# UPCNSL-ABS-PVC-DEP-1B.net
KiCad netlist of a schematic drawn in Altium Designer
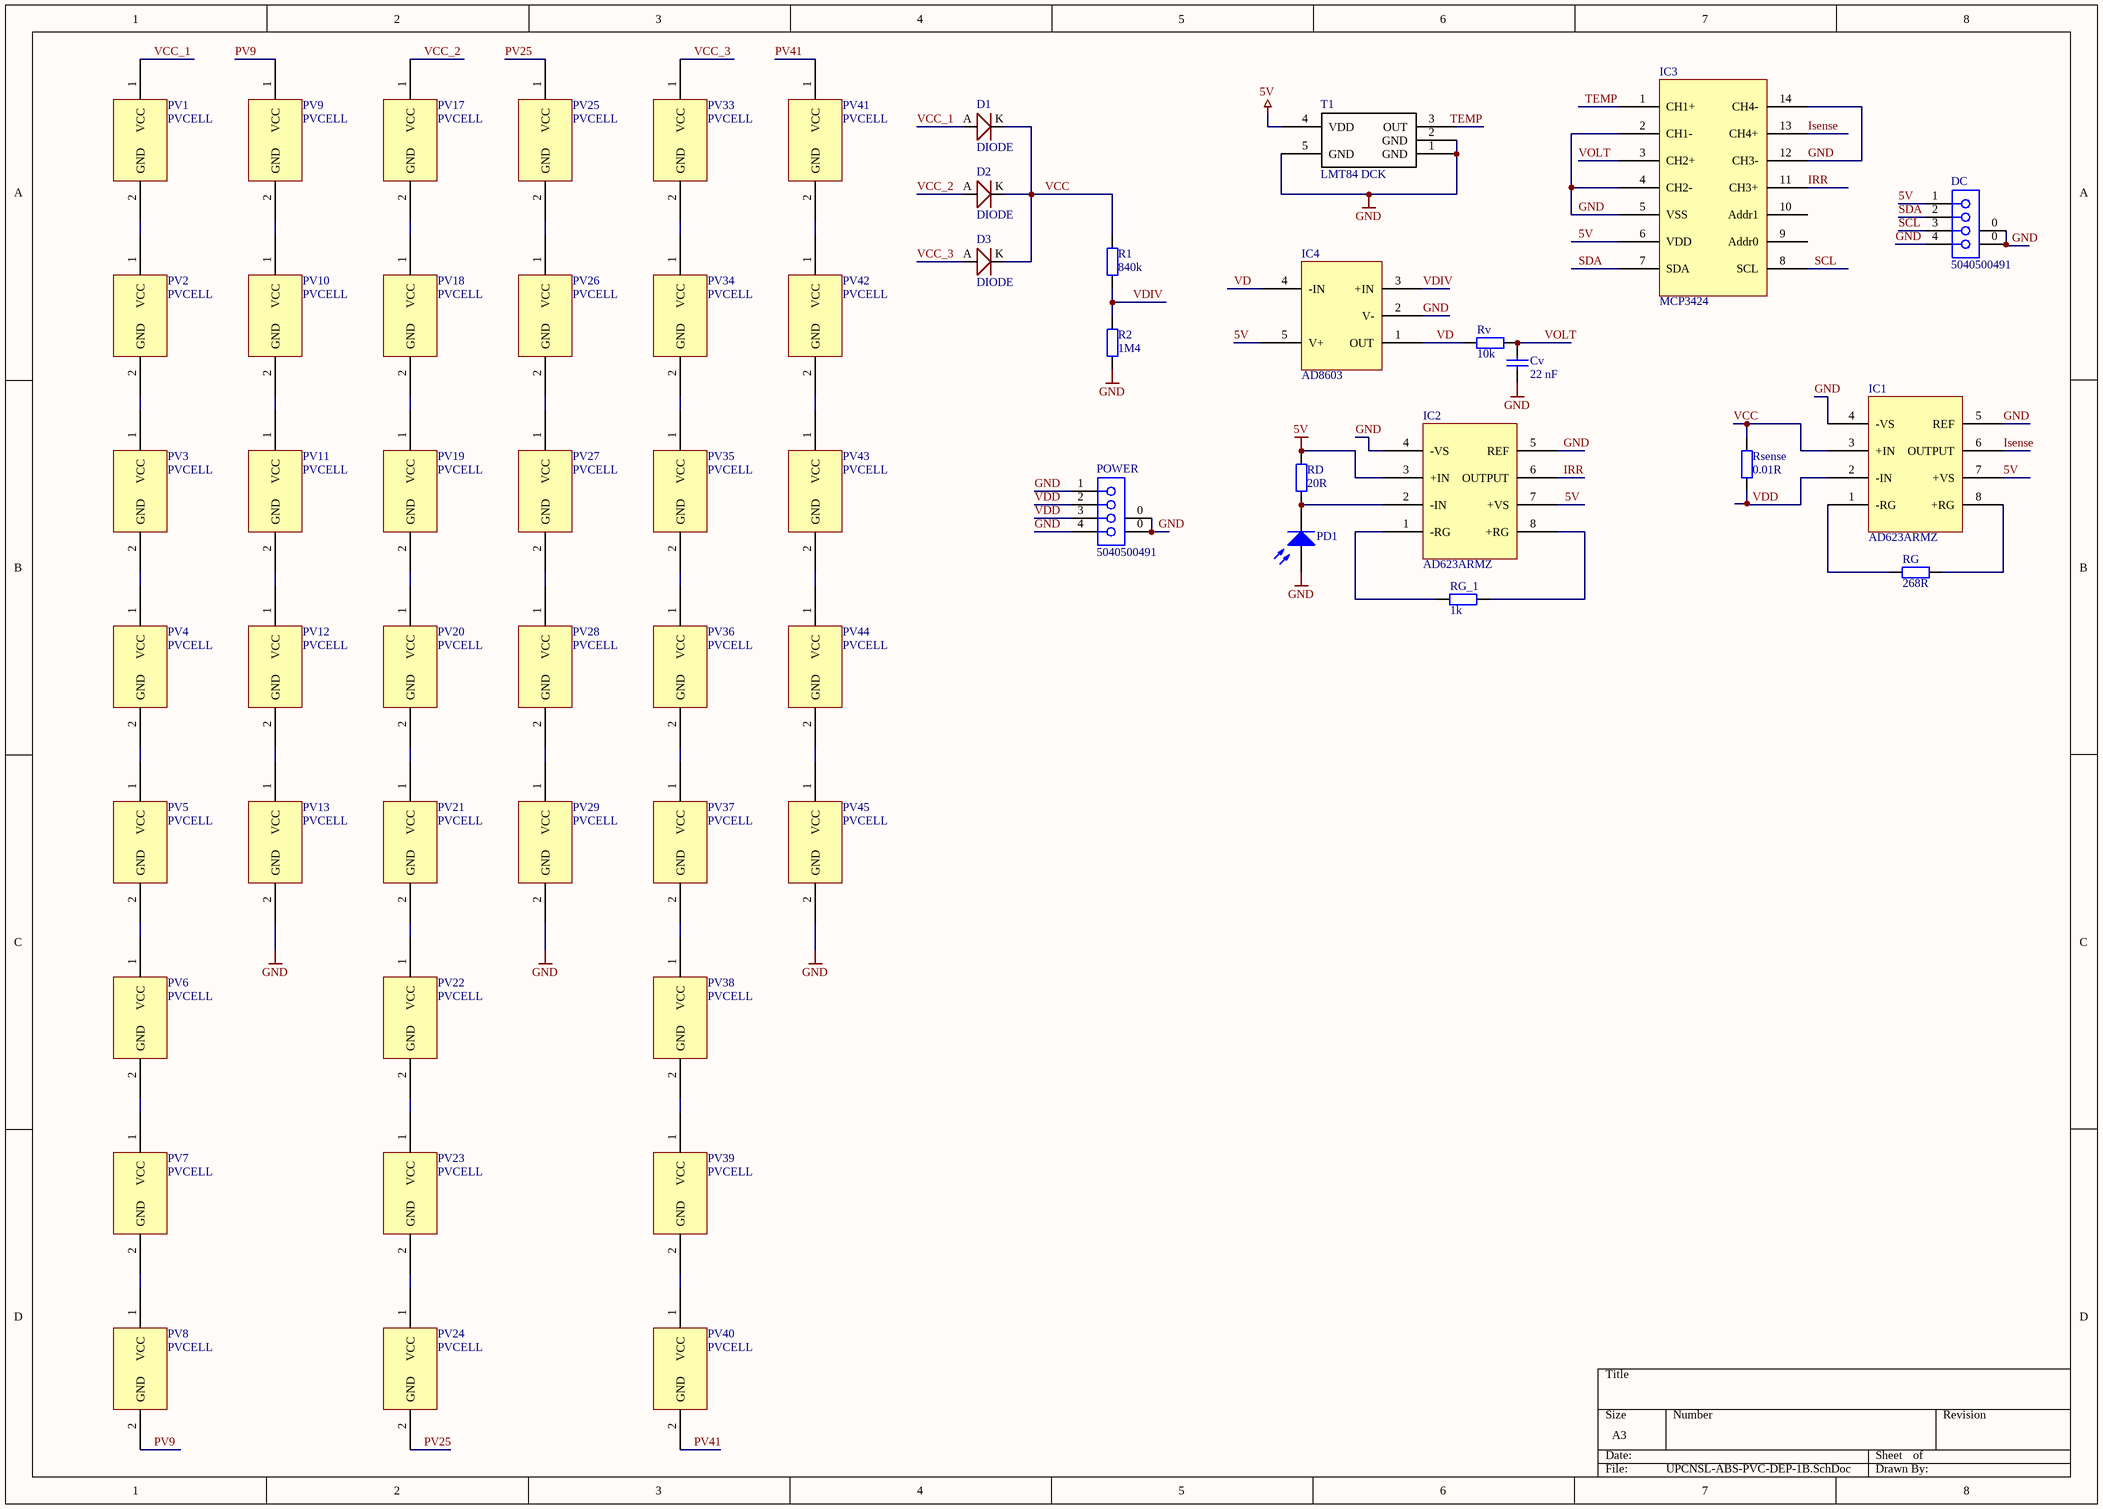
[diagram p0: UPCNSL-ABS-PVC-DEP-1B.SchDoc]

(export (version "E")
  (design (tool "Eeschema 10.0.6"))
  (components
    (comp (ref "Cv")
      (value "22 nF")
      (footprint "CAP0603")
      (description "Capacitor")
      (fields (field (name "Comment") "CAP0603"))
      (libsource (lib "UPCNSL-ABS-FLS-ARD_v1.2") (part "CAP0603"))
    )
    (comp (ref "D1")
      (value "DIODE")
      (footprint "(Schottky diode) SODFL160X70-2N")
      (libsource (lib "UPCNSL-ABS-FLS-ARD_v1.2") (part "DIODE"))
    )
    (comp (ref "D2")
      (value "DIODE")
      (footprint "(Schottky diode) SODFL160X70-2N")
      (libsource (lib "UPCNSL-ABS-FLS-ARD_v1.2") (part "DIODE"))
    )
    (comp (ref "D3")
      (value "DIODE")
      (footprint "(Schottky diode) SODFL160X70-2N")
      (libsource (lib "UPCNSL-ABS-FLS-ARD_v1.2") (part "DIODE"))
    )
    (comp (ref "DC")
      (value "5040500491")
      (footprint "5040500491")
      (libsource (lib "3CAT_Connectors") (part "MOLEX_5040500491"))
    )
    (comp (ref "IC1")
      (value "AD623ARMZ")
      (footprint "AD623ARMZ")
      (libsource (lib "UPCNSL-ABS-FLS-PVC") (part "AD623ARMZ"))
    )
    (comp (ref "IC2")
      (value "AD623ARMZ")
      (footprint "AD623ARMZ")
      (libsource (lib "UPCNSL-ABS-FLS-PVC") (part "AD623ARMZ"))
    )
    (comp (ref "IC3")
      (value "MCP3424")
      (footprint "MCP3424")
      (description "18-Bit, Multi-Channel ΔΣ Analog-to-Digital Converter with  I2C")
      (libsource (lib "UPCNSL-ABS-FLS-PVC") (part "MCP3424"))
    )
    (comp (ref "IC4")
      (value "AD8603")
      (footprint "AD8603")
      (libsource (lib "UPCNSL-ABS-FLS-PVC") (part "AD8603"))
    )
    (comp (ref "PD1")
      (value "Photo Sen")
      (footprint "C0805")
      (description "Photosensitive Diode")
      (fields (field (name "PUBLISHER") "Altium Limited"))
      (libsource (lib "Miscellaneous Devices") (part "Photo Sen"))
    )
    (comp (ref "POWER")
      (value "5040500491")
      (footprint "5040500491")
      (libsource (lib "3CAT_Connectors") (part "MOLEX_5040500491"))
    )
    (comp (ref "PV1")
      (value "PVCELL")
      (footprint "PV CELLS")
      (description "IXYS KXOB22-12X1L-ND")
      (libsource (lib "UPCNSL-ABS-FLS-PVC") (part "PVCELLS"))
    )
    (comp (ref "PV2")
      (value "PVCELL")
      (footprint "PV CELLS")
      (description "IXYS KXOB22-12X1L-ND")
      (libsource (lib "UPCNSL-ABS-FLS-PVC") (part "PVCELLS"))
    )
    (comp (ref "PV3")
      (value "PVCELL")
      (footprint "PV CELLS")
      (description "IXYS KXOB22-12X1L-ND")
      (libsource (lib "UPCNSL-ABS-FLS-PVC") (part "PVCELLS"))
    )
    (comp (ref "PV4")
      (value "PVCELL")
      (footprint "PV CELLS")
      (description "IXYS KXOB22-12X1L-ND")
      (libsource (lib "UPCNSL-ABS-FLS-PVC") (part "PVCELLS"))
    )
    (comp (ref "PV5")
      (value "PVCELL")
      (footprint "PV CELLS")
      (description "IXYS KXOB22-12X1L-ND")
      (libsource (lib "UPCNSL-ABS-FLS-PVC") (part "PVCELLS"))
    )
    (comp (ref "PV6")
      (value "PVCELL")
      (footprint "PV CELLS")
      (description "IXYS KXOB22-12X1L-ND")
      (libsource (lib "UPCNSL-ABS-FLS-PVC") (part "PVCELLS"))
    )
    (comp (ref "PV7")
      (value "PVCELL")
      (footprint "PV CELLS")
      (description "IXYS KXOB22-12X1L-ND")
      (libsource (lib "UPCNSL-ABS-FLS-PVC") (part "PVCELLS"))
    )
    (comp (ref "PV8")
      (value "PVCELL")
      (footprint "PV CELLS")
      (description "IXYS KXOB22-12X1L-ND")
      (libsource (lib "UPCNSL-ABS-FLS-PVC") (part "PVCELLS"))
    )
    (comp (ref "PV9")
      (value "PVCELL")
      (footprint "PV CELLS")
      (description "IXYS KXOB22-12X1L-ND")
      (libsource (lib "UPCNSL-ABS-FLS-PVC") (part "PVCELLS"))
    )
    (comp (ref "PV10")
      (value "PVCELL")
      (footprint "PV CELLS")
      (description "IXYS KXOB22-12X1L-ND")
      (libsource (lib "UPCNSL-ABS-FLS-PVC") (part "PVCELLS"))
    )
    (comp (ref "PV11")
      (value "PVCELL")
      (footprint "PV CELLS")
      (description "IXYS KXOB22-12X1L-ND")
      (libsource (lib "UPCNSL-ABS-FLS-PVC") (part "PVCELLS"))
    )
    (comp (ref "PV12")
      (value "PVCELL")
      (footprint "PV CELLS")
      (description "IXYS KXOB22-12X1L-ND")
      (libsource (lib "UPCNSL-ABS-FLS-PVC") (part "PVCELLS"))
    )
    (comp (ref "PV13")
      (value "PVCELL")
      (footprint "PV CELLS")
      (description "IXYS KXOB22-12X1L-ND")
      (libsource (lib "UPCNSL-ABS-FLS-PVC") (part "PVCELLS"))
    )
    (comp (ref "PV17")
      (value "PVCELL")
      (footprint "PV CELLS")
      (description "IXYS KXOB22-12X1L-ND")
      (libsource (lib "UPCNSL-ABS-FLS-PVC") (part "PVCELLS"))
    )
    (comp (ref "PV18")
      (value "PVCELL")
      (footprint "PV CELLS")
      (description "IXYS KXOB22-12X1L-ND")
      (libsource (lib "UPCNSL-ABS-FLS-PVC") (part "PVCELLS"))
    )
    (comp (ref "PV19")
      (value "PVCELL")
      (footprint "PV CELLS")
      (description "IXYS KXOB22-12X1L-ND")
      (libsource (lib "UPCNSL-ABS-FLS-PVC") (part "PVCELLS"))
    )
    (comp (ref "PV20")
      (value "PVCELL")
      (footprint "PV CELLS")
      (description "IXYS KXOB22-12X1L-ND")
      (libsource (lib "UPCNSL-ABS-FLS-PVC") (part "PVCELLS"))
    )
    (comp (ref "PV21")
      (value "PVCELL")
      (footprint "PV CELLS")
      (description "IXYS KXOB22-12X1L-ND")
      (libsource (lib "UPCNSL-ABS-FLS-PVC") (part "PVCELLS"))
    )
    (comp (ref "PV22")
      (value "PVCELL")
      (footprint "PV CELLS")
      (description "IXYS KXOB22-12X1L-ND")
      (libsource (lib "UPCNSL-ABS-FLS-PVC") (part "PVCELLS"))
    )
    (comp (ref "PV23")
      (value "PVCELL")
      (footprint "PV CELLS")
      (description "IXYS KXOB22-12X1L-ND")
      (libsource (lib "UPCNSL-ABS-FLS-PVC") (part "PVCELLS"))
    )
    (comp (ref "PV24")
      (value "PVCELL")
      (footprint "PV CELLS")
      (description "IXYS KXOB22-12X1L-ND")
      (libsource (lib "UPCNSL-ABS-FLS-PVC") (part "PVCELLS"))
    )
    (comp (ref "PV25")
      (value "PVCELL")
      (footprint "PV CELLS")
      (description "IXYS KXOB22-12X1L-ND")
      (libsource (lib "UPCNSL-ABS-FLS-PVC") (part "PVCELLS"))
    )
    (comp (ref "PV26")
      (value "PVCELL")
      (footprint "PV CELLS")
      (description "IXYS KXOB22-12X1L-ND")
      (libsource (lib "UPCNSL-ABS-FLS-PVC") (part "PVCELLS"))
    )
    (comp (ref "PV27")
      (value "PVCELL")
      (footprint "PV CELLS")
      (description "IXYS KXOB22-12X1L-ND")
      (libsource (lib "UPCNSL-ABS-FLS-PVC") (part "PVCELLS"))
    )
    (comp (ref "PV28")
      (value "PVCELL")
      (footprint "PV CELLS")
      (description "IXYS KXOB22-12X1L-ND")
      (libsource (lib "UPCNSL-ABS-FLS-PVC") (part "PVCELLS"))
    )
    (comp (ref "PV29")
      (value "PVCELL")
      (footprint "PV CELLS")
      (description "IXYS KXOB22-12X1L-ND")
      (libsource (lib "UPCNSL-ABS-FLS-PVC") (part "PVCELLS"))
    )
    (comp (ref "PV33")
      (value "PVCELL")
      (footprint "PV CELLS")
      (description "IXYS KXOB22-12X1L-ND")
      (libsource (lib "UPCNSL-ABS-FLS-PVC") (part "PVCELLS"))
    )
    (comp (ref "PV34")
      (value "PVCELL")
      (footprint "PV CELLS")
      (description "IXYS KXOB22-12X1L-ND")
      (libsource (lib "UPCNSL-ABS-FLS-PVC") (part "PVCELLS"))
    )
    (comp (ref "PV35")
      (value "PVCELL")
      (footprint "PV CELLS")
      (description "IXYS KXOB22-12X1L-ND")
      (libsource (lib "UPCNSL-ABS-FLS-PVC") (part "PVCELLS"))
    )
    (comp (ref "PV36")
      (value "PVCELL")
      (footprint "PV CELLS")
      (description "IXYS KXOB22-12X1L-ND")
      (libsource (lib "UPCNSL-ABS-FLS-PVC") (part "PVCELLS"))
    )
    (comp (ref "PV37")
      (value "PVCELL")
      (footprint "PV CELLS")
      (description "IXYS KXOB22-12X1L-ND")
      (libsource (lib "UPCNSL-ABS-FLS-PVC") (part "PVCELLS"))
    )
    (comp (ref "PV38")
      (value "PVCELL")
      (footprint "PV CELLS")
      (description "IXYS KXOB22-12X1L-ND")
      (libsource (lib "UPCNSL-ABS-FLS-PVC") (part "PVCELLS"))
    )
    (comp (ref "PV39")
      (value "PVCELL")
      (footprint "PV CELLS")
      (description "IXYS KXOB22-12X1L-ND")
      (libsource (lib "UPCNSL-ABS-FLS-PVC") (part "PVCELLS"))
    )
    (comp (ref "PV40")
      (value "PVCELL")
      (footprint "PV CELLS")
      (description "IXYS KXOB22-12X1L-ND")
      (libsource (lib "UPCNSL-ABS-FLS-PVC") (part "PVCELLS"))
    )
    (comp (ref "PV41")
      (value "PVCELL")
      (footprint "PV CELLS")
      (description "IXYS KXOB22-12X1L-ND")
      (libsource (lib "UPCNSL-ABS-FLS-PVC") (part "PVCELLS"))
    )
    (comp (ref "PV42")
      (value "PVCELL")
      (footprint "PV CELLS")
      (description "IXYS KXOB22-12X1L-ND")
      (libsource (lib "UPCNSL-ABS-FLS-PVC") (part "PVCELLS"))
    )
    (comp (ref "PV43")
      (value "PVCELL")
      (footprint "PV CELLS")
      (description "IXYS KXOB22-12X1L-ND")
      (libsource (lib "UPCNSL-ABS-FLS-PVC") (part "PVCELLS"))
    )
    (comp (ref "PV44")
      (value "PVCELL")
      (footprint "PV CELLS")
      (description "IXYS KXOB22-12X1L-ND")
      (libsource (lib "UPCNSL-ABS-FLS-PVC") (part "PVCELLS"))
    )
    (comp (ref "PV45")
      (value "PVCELL")
      (footprint "PV CELLS")
      (description "IXYS KXOB22-12X1L-ND")
      (libsource (lib "UPCNSL-ABS-FLS-PVC") (part "PVCELLS"))
    )
    (comp (ref "R1")
      (value "840k")
      (footprint "RES0603")
      (description "Resistor")
      (fields (field (name "Comment") "RES0603"))
      (libsource (lib "UPCNSL-ABS-FLS-ARD_v1.2") (part "RES0603"))
    )
    (comp (ref "R2")
      (value "1M4")
      (footprint "RES0603")
      (description "Resistor")
      (fields (field (name "Comment") "RES0603"))
      (libsource (lib "UPCNSL-ABS-FLS-ARD_v1.2") (part "RES0603"))
    )
    (comp (ref "RD")
      (value "20R")
      (footprint "RES0603")
      (description "Resistor")
      (fields (field (name "Comment") "RES0603"))
      (libsource (lib "UPCNSL-ABS-FLS-ARD_v1.2") (part "RES0603"))
    )
    (comp (ref "RG")
      (value "268R")
      (footprint "RES0603")
      (description "Resistor")
      (fields (field (name "Comment") "RES0603"))
      (libsource (lib "") (part "RES0603_1"))
    )
    (comp (ref "RG_1")
      (value "1k")
      (footprint "RES0603")
      (description "Resistor")
      (fields (field (name "Comment") "RES0603"))
      (libsource (lib "") (part "RES0603_1"))
    )
    (comp (ref "Rsense")
      (value "0.01R")
      (footprint "RES0603")
      (description "Resistor")
      (fields (field (name "Comment") "RES0603"))
      (libsource (lib "UPCNSL-ABS-FLS-ARD_v1.2") (part "RES0603"))
    )
    (comp (ref "Rv")
      (value "10k")
      (footprint "RES0603")
      (description "Resistor")
      (fields (field (name "Comment") "RES0603"))
      (libsource (lib "") (part "RES0603_1"))
    )
    (comp (ref "T1")
      (value "LMT84 DCK")
      (footprint "DCK/SOT65P210X110-5N")
      (libsource (lib "UPCNSL-ABS-FLS-PVC") (part "LMT84 DCK"))
    )
  )
  (nets
    (net (code "1") (name "/IRR") (class "Default")
      (node (ref "IC2") (pin "6") (pinfunction "OUTPUT_6") (pintype "passive"))
      (node (ref "IC3") (pin "11") (pinfunction "CH3+_11") (pintype "passive"))
    )
    (net (code "2") (name "/Isense") (class "Default")
      (node (ref "IC1") (pin "6") (pinfunction "OUTPUT_6") (pintype "passive"))
      (node (ref "IC3") (pin "13") (pinfunction "CH4+_13") (pintype "passive"))
    )
    (net (code "3") (name "/PV9") (class "Default")
      (node (ref "PV8") (pin "2") (pinfunction "GND_2") (pintype "passive"))
      (node (ref "PV9") (pin "1") (pinfunction "VCC_1") (pintype "passive"))
    )
    (net (code "4") (name "/PV25") (class "Default")
      (node (ref "PV24") (pin "2") (pinfunction "GND_2") (pintype "passive"))
      (node (ref "PV25") (pin "1") (pinfunction "VCC_1") (pintype "passive"))
    )
    (net (code "5") (name "/PV41") (class "Default")
      (node (ref "PV40") (pin "2") (pinfunction "GND_2") (pintype "passive"))
      (node (ref "PV41") (pin "1") (pinfunction "VCC_1") (pintype "passive"))
    )
    (net (code "6") (name "/SCL") (class "Default")
      (node (ref "DC") (pin "3") (pinfunction "3_3") (pintype "passive"))
      (node (ref "IC3") (pin "8") (pinfunction "SCL_8") (pintype "passive"))
    )
    (net (code "7") (name "/SDA") (class "Default")
      (node (ref "DC") (pin "2") (pinfunction "2_2") (pintype "passive"))
      (node (ref "IC3") (pin "7") (pinfunction "SDA_7") (pintype "passive"))
    )
    (net (code "8") (name "/TEMP") (class "Default")
      (node (ref "IC3") (pin "1") (pinfunction "CH1+_1") (pintype "passive"))
    )
    (net (code "9") (name "/VCC") (class "Default")
      (node (ref "D1") (pin "K") (pinfunction "K_K") (pintype "passive"))
      (node (ref "D2") (pin "K") (pinfunction "K_K") (pintype "passive"))
      (node (ref "D3") (pin "K") (pinfunction "K_K") (pintype "passive"))
      (node (ref "IC1") (pin "3") (pinfunction "+IN_3") (pintype "passive"))
      (node (ref "R1") (pin "2") (pinfunction "2_2") (pintype "passive"))
      (node (ref "Rsense") (pin "2") (pinfunction "2_2") (pintype "passive"))
    )
    (net (code "10") (name "/VCC_1") (class "Default")
      (node (ref "D1") (pin "A") (pinfunction "A_A") (pintype "passive"))
      (node (ref "PV1") (pin "1") (pinfunction "VCC_1") (pintype "passive"))
    )
    (net (code "11") (name "/VCC_2") (class "Default")
      (node (ref "D2") (pin "A") (pinfunction "A_A") (pintype "passive"))
      (node (ref "PV17") (pin "1") (pinfunction "VCC_1") (pintype "passive"))
    )
    (net (code "12") (name "/VCC_3") (class "Default")
      (node (ref "D3") (pin "A") (pinfunction "A_A") (pintype "passive"))
      (node (ref "PV33") (pin "1") (pinfunction "VCC_1") (pintype "passive"))
    )
    (net (code "13") (name "/VD") (class "Default")
      (node (ref "IC4") (pin "1") (pinfunction "OUT_1") (pintype "passive"))
      (node (ref "IC4") (pin "4") (pinfunction "-IN_4") (pintype "passive"))
      (node (ref "Rv") (pin "1") (pinfunction "1_1") (pintype "passive"))
    )
    (net (code "14") (name "/VDD") (class "Default")
      (node (ref "IC1") (pin "2") (pinfunction "-IN_2") (pintype "passive"))
      (node (ref "POWER") (pin "2") (pinfunction "2_2") (pintype "passive"))
      (node (ref "POWER") (pin "3") (pinfunction "3_3") (pintype "passive"))
      (node (ref "Rsense") (pin "1") (pinfunction "1_1") (pintype "passive"))
    )
    (net (code "15") (name "/VDIV") (class "Default")
      (node (ref "IC4") (pin "3") (pinfunction "+IN_3") (pintype "passive"))
      (node (ref "R1") (pin "1") (pinfunction "1_1") (pintype "passive"))
      (node (ref "R2") (pin "2") (pinfunction "2_2") (pintype "passive"))
    )
    (net (code "16") (name "/VOLT") (class "Default")
      (node (ref "Cv") (pin "2") (pinfunction "2_2") (pintype "passive"))
      (node (ref "IC3") (pin "3") (pinfunction "CH2+_3") (pintype "passive"))
      (node (ref "Rv") (pin "2") (pinfunction "2_2") (pintype "passive"))
    )
    (net (code "17") (name "5V") (class "Default")
      (node (ref "DC") (pin "1") (pinfunction "1_1") (pintype "passive"))
      (node (ref "IC1") (pin "7") (pinfunction "+VS_7") (pintype "passive"))
      (node (ref "IC2") (pin "3") (pinfunction "+IN_3") (pintype "passive"))
      (node (ref "IC2") (pin "7") (pinfunction "+VS_7") (pintype "passive"))
      (node (ref "IC3") (pin "6") (pinfunction "VDD_6") (pintype "passive"))
      (node (ref "IC4") (pin "5") (pinfunction "V+_5") (pintype "passive"))
      (node (ref "RD") (pin "2") (pinfunction "2_2") (pintype "passive"))
      (node (ref "T1") (pin "4") (pinfunction "VDD_4") (pintype "passive"))
    )
    (net (code "18") (name "GND") (class "Default")
      (node (ref "Cv") (pin "1") (pinfunction "1_1") (pintype "passive"))
      (node (ref "DC") (pin "0") (pinfunction "MH1_0") (pintype "passive"))
      (node (ref "DC") (pin "4") (pinfunction "4_4") (pintype "passive"))
      (node (ref "IC1") (pin "4") (pinfunction "-VS_4") (pintype "passive"))
      (node (ref "IC1") (pin "5") (pinfunction "REF_5") (pintype "passive"))
      (node (ref "IC2") (pin "4") (pinfunction "-VS_4") (pintype "passive"))
      (node (ref "IC2") (pin "5") (pinfunction "REF_5") (pintype "passive"))
      (node (ref "IC3") (pin "12") (pinfunction "CH3-_12") (pintype "passive"))
      (node (ref "IC3") (pin "14") (pinfunction "CH4-_14") (pintype "passive"))
      (node (ref "IC3") (pin "2") (pinfunction "CH1-_2") (pintype "passive"))
      (node (ref "IC3") (pin "4") (pinfunction "CH2-_4") (pintype "passive"))
      (node (ref "IC3") (pin "5") (pinfunction "VSS_5") (pintype "passive"))
      (node (ref "IC4") (pin "2") (pinfunction "V-_2") (pintype "passive"))
      (node (ref "PD1") (pin "1") (pinfunction "A_1") (pintype "passive"))
      (node (ref "POWER") (pin "0") (pinfunction "MH2_0") (pintype "passive"))
      (node (ref "POWER") (pin "1") (pinfunction "1_1") (pintype "passive"))
      (node (ref "POWER") (pin "4") (pinfunction "4_4") (pintype "passive"))
      (node (ref "PV13") (pin "2") (pinfunction "GND_2") (pintype "passive"))
      (node (ref "PV29") (pin "2") (pinfunction "GND_2") (pintype "passive"))
      (node (ref "PV45") (pin "2") (pinfunction "GND_2") (pintype "passive"))
      (node (ref "R2") (pin "1") (pinfunction "1_1") (pintype "passive"))
      (node (ref "T1") (pin "1") (pinfunction "GND_1") (pintype "passive"))
      (node (ref "T1") (pin "2") (pinfunction "GND_2") (pintype "passive"))
      (node (ref "T1") (pin "5") (pinfunction "GND_5") (pintype "passive"))
    )
    (net (code "19") (name "Net-(IC1-+RG)") (class "Default")
      (node (ref "IC1") (pin "8") (pinfunction "+RG_8") (pintype "passive"))
      (node (ref "RG") (pin "2") (pinfunction "2_2") (pintype "passive"))
    )
    (net (code "20") (name "Net-(IC1--RG)") (class "Default")
      (node (ref "IC1") (pin "1") (pinfunction "-RG_1") (pintype "passive"))
      (node (ref "RG") (pin "1") (pinfunction "1_1") (pintype "passive"))
    )
    (net (code "21") (name "Net-(IC2-+RG)") (class "Default")
      (node (ref "IC2") (pin "8") (pinfunction "+RG_8") (pintype "passive"))
      (node (ref "RG_1") (pin "2") (pinfunction "2_2") (pintype "passive"))
    )
    (net (code "22") (name "Net-(IC2--IN)") (class "Default")
      (node (ref "IC2") (pin "2") (pinfunction "-IN_2") (pintype "passive"))
      (node (ref "PD1") (pin "2") (pinfunction "K_2") (pintype "passive"))
      (node (ref "RD") (pin "1") (pinfunction "1_1") (pintype "passive"))
    )
    (net (code "23") (name "Net-(IC2--RG)") (class "Default")
      (node (ref "IC2") (pin "1") (pinfunction "-RG_1") (pintype "passive"))
      (node (ref "RG_1") (pin "1") (pinfunction "1_1") (pintype "passive"))
    )
    (net (code "24") (name "Net-(PV1-GND)") (class "Default")
      (node (ref "PV1") (pin "2") (pinfunction "GND_2") (pintype "passive"))
      (node (ref "PV2") (pin "1") (pinfunction "VCC_1") (pintype "passive"))
    )
    (net (code "25") (name "Net-(PV2-GND)") (class "Default")
      (node (ref "PV2") (pin "2") (pinfunction "GND_2") (pintype "passive"))
      (node (ref "PV3") (pin "1") (pinfunction "VCC_1") (pintype "passive"))
    )
    (net (code "26") (name "Net-(PV3-GND)") (class "Default")
      (node (ref "PV3") (pin "2") (pinfunction "GND_2") (pintype "passive"))
      (node (ref "PV4") (pin "1") (pinfunction "VCC_1") (pintype "passive"))
    )
    (net (code "27") (name "Net-(PV4-GND)") (class "Default")
      (node (ref "PV4") (pin "2") (pinfunction "GND_2") (pintype "passive"))
      (node (ref "PV5") (pin "1") (pinfunction "VCC_1") (pintype "passive"))
    )
    (net (code "28") (name "Net-(PV5-GND)") (class "Default")
      (node (ref "PV5") (pin "2") (pinfunction "GND_2") (pintype "passive"))
      (node (ref "PV6") (pin "1") (pinfunction "VCC_1") (pintype "passive"))
    )
    (net (code "29") (name "Net-(PV6-GND)") (class "Default")
      (node (ref "PV6") (pin "2") (pinfunction "GND_2") (pintype "passive"))
      (node (ref "PV7") (pin "1") (pinfunction "VCC_1") (pintype "passive"))
    )
    (net (code "30") (name "Net-(PV7-GND)") (class "Default")
      (node (ref "PV7") (pin "2") (pinfunction "GND_2") (pintype "passive"))
      (node (ref "PV8") (pin "1") (pinfunction "VCC_1") (pintype "passive"))
    )
    (net (code "31") (name "Net-(PV10-GND)") (class "Default")
      (node (ref "PV10") (pin "2") (pinfunction "GND_2") (pintype "passive"))
      (node (ref "PV11") (pin "1") (pinfunction "VCC_1") (pintype "passive"))
    )
    (net (code "32") (name "Net-(PV10-VCC)") (class "Default")
      (node (ref "PV10") (pin "1") (pinfunction "VCC_1") (pintype "passive"))
      (node (ref "PV9") (pin "2") (pinfunction "GND_2") (pintype "passive"))
    )
    (net (code "33") (name "Net-(PV11-GND)") (class "Default")
      (node (ref "PV11") (pin "2") (pinfunction "GND_2") (pintype "passive"))
      (node (ref "PV12") (pin "1") (pinfunction "VCC_1") (pintype "passive"))
    )
    (net (code "34") (name "Net-(PV12-GND)") (class "Default")
      (node (ref "PV12") (pin "2") (pinfunction "GND_2") (pintype "passive"))
      (node (ref "PV13") (pin "1") (pinfunction "VCC_1") (pintype "passive"))
    )
    (net (code "35") (name "Net-(PV17-GND)") (class "Default")
      (node (ref "PV17") (pin "2") (pinfunction "GND_2") (pintype "passive"))
      (node (ref "PV18") (pin "1") (pinfunction "VCC_1") (pintype "passive"))
    )
    (net (code "36") (name "Net-(PV18-GND)") (class "Default")
      (node (ref "PV18") (pin "2") (pinfunction "GND_2") (pintype "passive"))
      (node (ref "PV19") (pin "1") (pinfunction "VCC_1") (pintype "passive"))
    )
    (net (code "37") (name "Net-(PV19-GND)") (class "Default")
      (node (ref "PV19") (pin "2") (pinfunction "GND_2") (pintype "passive"))
      (node (ref "PV20") (pin "1") (pinfunction "VCC_1") (pintype "passive"))
    )
    (net (code "38") (name "Net-(PV20-GND)") (class "Default")
      (node (ref "PV20") (pin "2") (pinfunction "GND_2") (pintype "passive"))
      (node (ref "PV21") (pin "1") (pinfunction "VCC_1") (pintype "passive"))
    )
    (net (code "39") (name "Net-(PV21-GND)") (class "Default")
      (node (ref "PV21") (pin "2") (pinfunction "GND_2") (pintype "passive"))
      (node (ref "PV22") (pin "1") (pinfunction "VCC_1") (pintype "passive"))
    )
    (net (code "40") (name "Net-(PV22-GND)") (class "Default")
      (node (ref "PV22") (pin "2") (pinfunction "GND_2") (pintype "passive"))
      (node (ref "PV23") (pin "1") (pinfunction "VCC_1") (pintype "passive"))
    )
    (net (code "41") (name "Net-(PV23-GND)") (class "Default")
      (node (ref "PV23") (pin "2") (pinfunction "GND_2") (pintype "passive"))
      (node (ref "PV24") (pin "1") (pinfunction "VCC_1") (pintype "passive"))
    )
    (net (code "42") (name "Net-(PV25-GND)") (class "Default")
      (node (ref "PV25") (pin "2") (pinfunction "GND_2") (pintype "passive"))
      (node (ref "PV26") (pin "1") (pinfunction "VCC_1") (pintype "passive"))
    )
    (net (code "43") (name "Net-(PV26-GND)") (class "Default")
      (node (ref "PV26") (pin "2") (pinfunction "GND_2") (pintype "passive"))
      (node (ref "PV27") (pin "1") (pinfunction "VCC_1") (pintype "passive"))
    )
    (net (code "44") (name "Net-(PV27-GND)") (class "Default")
      (node (ref "PV27") (pin "2") (pinfunction "GND_2") (pintype "passive"))
      (node (ref "PV28") (pin "1") (pinfunction "VCC_1") (pintype "passive"))
    )
    (net (code "45") (name "Net-(PV28-GND)") (class "Default")
      (node (ref "PV28") (pin "2") (pinfunction "GND_2") (pintype "passive"))
      (node (ref "PV29") (pin "1") (pinfunction "VCC_1") (pintype "passive"))
    )
    (net (code "46") (name "Net-(PV33-GND)") (class "Default")
      (node (ref "PV33") (pin "2") (pinfunction "GND_2") (pintype "passive"))
      (node (ref "PV34") (pin "1") (pinfunction "VCC_1") (pintype "passive"))
    )
    (net (code "47") (name "Net-(PV34-GND)") (class "Default")
      (node (ref "PV34") (pin "2") (pinfunction "GND_2") (pintype "passive"))
      (node (ref "PV35") (pin "1") (pinfunction "VCC_1") (pintype "passive"))
    )
    (net (code "48") (name "Net-(PV35-GND)") (class "Default")
      (node (ref "PV35") (pin "2") (pinfunction "GND_2") (pintype "passive"))
      (node (ref "PV36") (pin "1") (pinfunction "VCC_1") (pintype "passive"))
    )
    (net (code "49") (name "Net-(PV36-GND)") (class "Default")
      (node (ref "PV36") (pin "2") (pinfunction "GND_2") (pintype "passive"))
      (node (ref "PV37") (pin "1") (pinfunction "VCC_1") (pintype "passive"))
    )
    (net (code "50") (name "Net-(PV37-GND)") (class "Default")
      (node (ref "PV37") (pin "2") (pinfunction "GND_2") (pintype "passive"))
      (node (ref "PV38") (pin "1") (pinfunction "VCC_1") (pintype "passive"))
    )
    (net (code "51") (name "Net-(PV38-GND)") (class "Default")
      (node (ref "PV38") (pin "2") (pinfunction "GND_2") (pintype "passive"))
      (node (ref "PV39") (pin "1") (pinfunction "VCC_1") (pintype "passive"))
    )
    (net (code "52") (name "Net-(PV39-GND)") (class "Default")
      (node (ref "PV39") (pin "2") (pinfunction "GND_2") (pintype "passive"))
      (node (ref "PV40") (pin "1") (pinfunction "VCC_1") (pintype "passive"))
    )
    (net (code "53") (name "Net-(PV41-GND)") (class "Default")
      (node (ref "PV41") (pin "2") (pinfunction "GND_2") (pintype "passive"))
      (node (ref "PV42") (pin "1") (pinfunction "VCC_1") (pintype "passive"))
    )
    (net (code "54") (name "Net-(PV42-GND)") (class "Default")
      (node (ref "PV42") (pin "2") (pinfunction "GND_2") (pintype "passive"))
      (node (ref "PV43") (pin "1") (pinfunction "VCC_1") (pintype "passive"))
    )
    (net (code "55") (name "Net-(PV43-GND)") (class "Default")
      (node (ref "PV43") (pin "2") (pinfunction "GND_2") (pintype "passive"))
      (node (ref "PV44") (pin "1") (pinfunction "VCC_1") (pintype "passive"))
    )
    (net (code "56") (name "Net-(PV44-GND)") (class "Default")
      (node (ref "PV44") (pin "2") (pinfunction "GND_2") (pintype "passive"))
      (node (ref "PV45") (pin "1") (pinfunction "VCC_1") (pintype "passive"))
    )
    (net (code "57") (name "unconnected-(IC3-Addr0-Pad9)") (class "Default")
      (node (ref "IC3") (pin "9") (pinfunction "Addr0_9") (pintype "passive"))
    )
    (net (code "58") (name "unconnected-(IC3-Addr1-Pad10)") (class "Default")
      (node (ref "IC3") (pin "10") (pinfunction "Addr1_10") (pintype "passive"))
    )
    (net (code "59") (name "unconnected-(T1-OUT-Pad3)") (class "Default")
      (node (ref "T1") (pin "3") (pinfunction "OUT_3") (pintype "passive"))
    )
  )
)
